# H0BR4.net
KiCad netlist of a schematic drawn in EAGLE
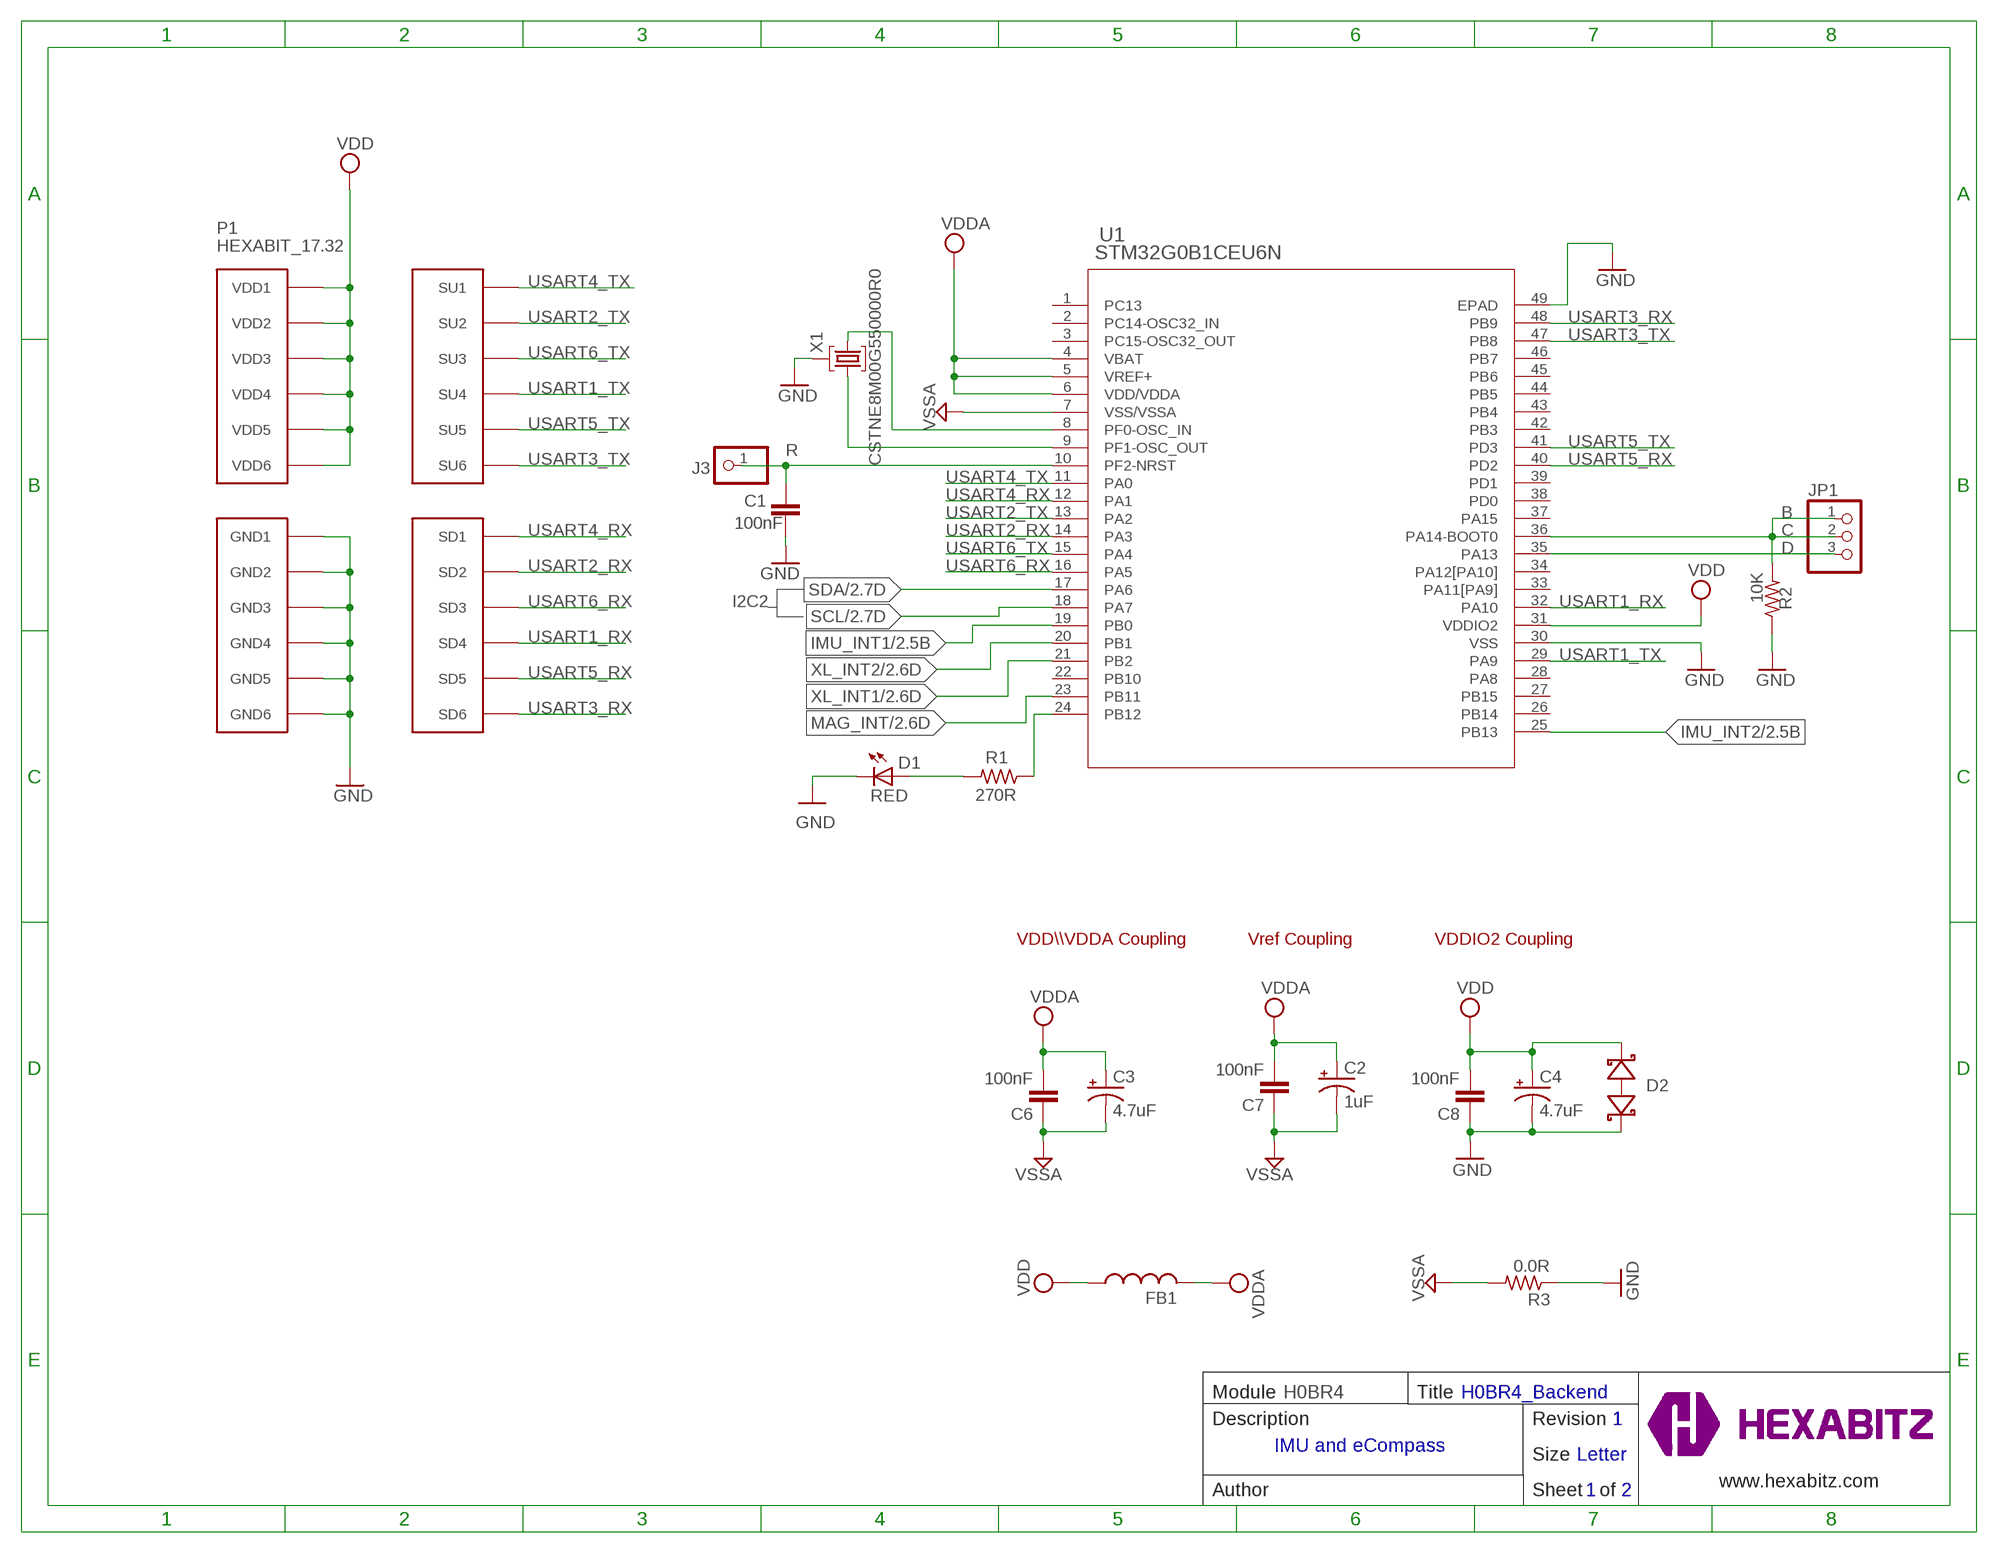
[diagram p0: schematic, sheet 1]
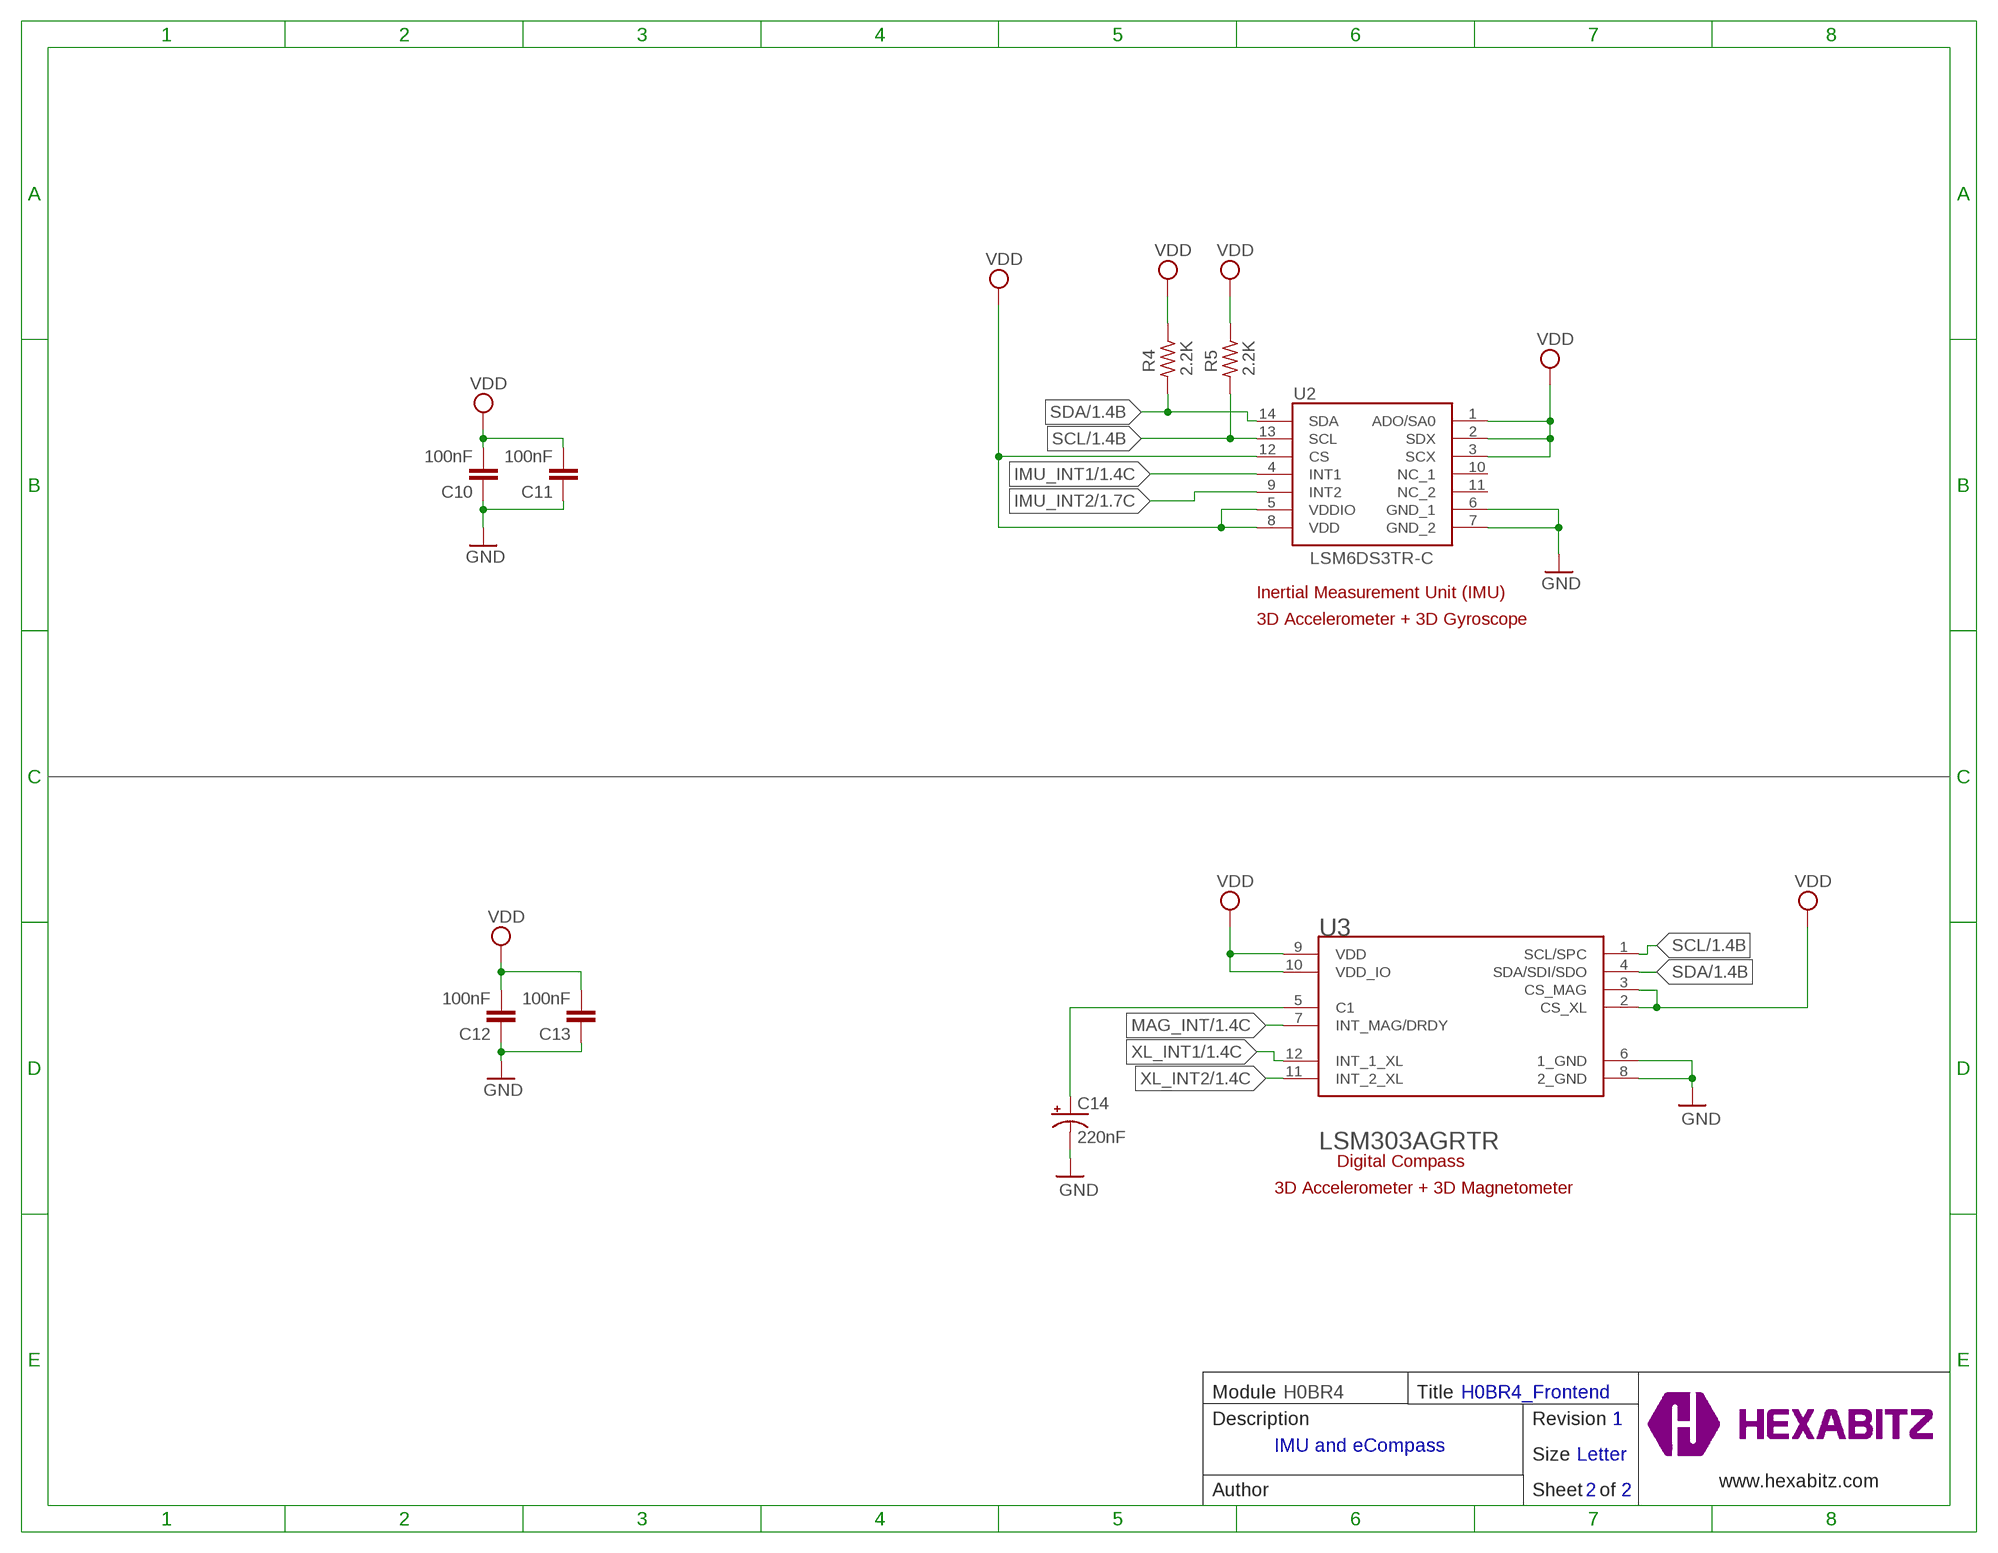
[diagram p1: schematic, sheet 2]

(export (version "E")
  (design (tool "Eeschema 10.0.6"))
  (components
    (comp (ref "C10")
      (value "100nF")
      (footprint "eagle-import:C-0603")
      (fields
        (field (name "CAPACITANCE") "100nF")
        (field (name "MFN") "AVX CORPORATION")
        (field (name "MPN") "'0603YC104K4T2A")
        (field (name "OCTOPART_URL") "'https://octopart.com/0603yc104k4t2a-avx+interconnect+%2F+elco-8120651")
        (field (name "TOLERANCE") "10%")
        (field (name "VOLTAGE_RATING") "16.0 V")
      )
      (libsource (lib "eagle-import") (part "C-0603"))
    )
    (comp (ref "C11")
      (value "100nF")
      (footprint "eagle-import:C-0603")
      (fields
        (field (name "CAPACITANCE") "100nF")
        (field (name "MFN") "AVX CORPORATION")
        (field (name "MPN") "'0603YC104K4T2A")
        (field (name "OCTOPART_URL") "'https://octopart.com/0603yc104k4t2a-avx+interconnect+%2F+elco-8120651")
        (field (name "TOLERANCE") "10%")
        (field (name "VOLTAGE_RATING") "16.0 V")
      )
      (libsource (lib "eagle-import") (part "C-0603"))
    )
    (comp (ref "C12")
      (value "100nF")
      (footprint "eagle-import:C-0603")
      (fields
        (field (name "CAPACITANCE") "100nF")
        (field (name "MFN") "AVX CORPORATION")
        (field (name "MPN") "'0603YC104K4T2A")
        (field (name "OCTOPART_URL") "'https://octopart.com/0603yc104k4t2a-avx+interconnect+%2F+elco-8120651")
        (field (name "TOLERANCE") "10%")
        (field (name "VOLTAGE_RATING") "16.0 V")
      )
      (libsource (lib "eagle-import") (part "C-0603"))
    )
    (comp (ref "C13")
      (value "100nF")
      (footprint "eagle-import:C-0603")
      (fields
        (field (name "CAPACITANCE") "100nF")
        (field (name "MFN") "AVX CORPORATION")
        (field (name "MPN") "'0603YC104K4T2A")
        (field (name "OCTOPART_URL") "'https://octopart.com/0603yc104k4t2a-avx+interconnect+%2F+elco-8120651")
        (field (name "TOLERANCE") "10%")
        (field (name "VOLTAGE_RATING") "16.0 V")
      )
      (libsource (lib "eagle-import") (part "C-0603"))
    )
    (comp (ref "C14")
      (value "220nF")
      (footprint "eagle-import:C-0805-POL")
      (fields
        (field (name "CAPACITANCE") "4.7uF")
        (field (name "MFN") "KEMET ")
        (field (name "MPN") "C0805C224K1RACTU")
        (field (name "OCTOPART_URL") "https://octopart.com/c0805c224k1ractu-kemet-12818106?r=sp")
        (field (name "TOLERANCE") "20%")
        (field (name "VOLTAGE_RATING") "10.0 V")
      )
      (libsource (lib "eagle-import") (part "C-0805-POL"))
    )
    (comp (ref "R4")
      (value "2.2K")
      (footprint "eagle-import:R-0603")
      (fields
        (field (name "MFN") "Yageo")
        (field (name "MPN") "RC0603FR-072K2L")
        (field (name "OCTOPART_URL") "https://octopart.com/rc0603fr-072k2l-yageo-1214512?r=sp")
        (field (name "RESISTANCE") "2.2K Ohm")
        (field (name "TOLERANCE") "5%")
      )
      (libsource (lib "eagle-import") (part "R-0603"))
    )
    (comp (ref "R5")
      (value "2.2K")
      (footprint "eagle-import:R-0603")
      (fields
        (field (name "MFN") "Yageo")
        (field (name "MPN") "RC0603FR-072K2L")
        (field (name "OCTOPART_URL") "https://octopart.com/rc0603fr-072k2l-yageo-1214512?r=sp")
        (field (name "RESISTANCE") "2.2K Ohm")
        (field (name "TOLERANCE") "5%")
      )
      (libsource (lib "eagle-import") (part "R-0603"))
    )
    (comp (ref "U2")
      (value "LSM6DS3TR-C")
      (footprint "eagle-import:LGA-14(2.5X3X0.86)")
      (libsource (lib "eagle-import") (part "LSM6DS3TR-C"))
    )
    (comp (ref "U3")
      (value "STMICROELECTRONICS_LSM303AGRTRSTMICROELECTRONICS_LSM303AGRTR_0_0")
      (footprint "eagle-import:STMICROELECTRONICS_LSM303AGRTR_0")
      (fields
        (field (name "DIGIKEY_PART_NUMBER") "497-16527-1-ND")
        (field (name "MOUSER_PART_NUMBER") "511-LSM303AGRTR")
        (field (name "MPN") "LSM303AGRTR")
      )
      (libsource (lib "eagle-import") (part "STMICROELECTRONICS_LSM303AGRTRSTMICROELECTRONICS_LSM303AGRTR_0_0"))
    )
    (comp (ref "C1")
      (value "100nF")
      (footprint "eagle-import:C-0603")
      (fields
        (field (name "CAPACITANCE") "100nF")
        (field (name "MFN") "AVX CORPORATION")
        (field (name "MPN") "'0603YC104K4T2A")
        (field (name "OCTOPART_URL") "'https://octopart.com/0603yc104k4t2a-avx+interconnect+%2F+elco-8120651")
        (field (name "TOLERANCE") "10%")
        (field (name "VOLTAGE_RATING") "16.0 V")
      )
      (libsource (lib "eagle-import") (part "C-0603"))
    )
    (comp (ref "C2")
      (value "1uF")
      (footprint "eagle-import:C-0805-POL")
      (fields
        (field (name "CAPACITANCE") "1.00uF")
        (field (name "MFN") "'YAGEO [VA]")
        (field (name "MPN") "'CC0805KKX7R7BB105")
        (field (name "OCTOPART_URL") "https://octopart.com/cc0805kkx7r7bb105-yageo-8376555?r=sp")
        (field (name "TOLERANCE") "10%")
        (field (name "VOLTAGE_RATING") "16.0 V")
      )
      (libsource (lib "eagle-import") (part "C-0805-POL"))
    )
    (comp (ref "C3")
      (value "4.7uF")
      (footprint "eagle-import:C-0805-POL")
      (fields
        (field (name "CAPACITANCE") "4.7uF")
        (field (name "MFN") "Panasonic")
        (field (name "MPN") "10TPU4R7MSI")
        (field (name "OCTOPART_URL") "https://octopart.com/10tpu4r7msi-panasonic-29487748")
        (field (name "TOLERANCE") "20%")
        (field (name "VOLTAGE_RATING") "10.0 V")
      )
      (libsource (lib "eagle-import") (part "C-0805-POL"))
    )
    (comp (ref "C4")
      (value "4.7uF")
      (footprint "eagle-import:C-0805-POL")
      (fields
        (field (name "CAPACITANCE") "4.7uF")
        (field (name "MFN") "Panasonic")
        (field (name "MPN") "10TPU4R7MSI")
        (field (name "OCTOPART_URL") "https://octopart.com/10tpu4r7msi-panasonic-29487748")
        (field (name "TOLERANCE") "20%")
        (field (name "VOLTAGE_RATING") "10.0 V")
      )
      (libsource (lib "eagle-import") (part "C-0805-POL"))
    )
    (comp (ref "C6")
      (value "100nF")
      (footprint "eagle-import:C-0603")
      (fields
        (field (name "CAPACITANCE") "100nF")
        (field (name "MFN") "AVX CORPORATION")
        (field (name "MPN") "'0603YC104K4T2A")
        (field (name "OCTOPART_URL") "'https://octopart.com/0603yc104k4t2a-avx+interconnect+%2F+elco-8120651")
        (field (name "TOLERANCE") "10%")
        (field (name "VOLTAGE_RATING") "16.0 V")
      )
      (libsource (lib "eagle-import") (part "C-0603"))
    )
    (comp (ref "C7")
      (value "100nF")
      (footprint "eagle-import:C-0603")
      (fields
        (field (name "CAPACITANCE") "100nF")
        (field (name "MFN") "AVX CORPORATION")
        (field (name "MPN") "'0603YC104K4T2A")
        (field (name "OCTOPART_URL") "'https://octopart.com/0603yc104k4t2a-avx+interconnect+%2F+elco-8120651")
        (field (name "TOLERANCE") "10%")
        (field (name "VOLTAGE_RATING") "16.0 V")
      )
      (libsource (lib "eagle-import") (part "C-0603"))
    )
    (comp (ref "C8")
      (value "100nF")
      (footprint "eagle-import:C-0603")
      (fields
        (field (name "CAPACITANCE") "100nF")
        (field (name "MFN") "AVX CORPORATION")
        (field (name "MPN") "'0603YC104K4T2A")
        (field (name "OCTOPART_URL") "'https://octopart.com/0603yc104k4t2a-avx+interconnect+%2F+elco-8120651")
        (field (name "TOLERANCE") "10%")
        (field (name "VOLTAGE_RATING") "16.0 V")
      )
      (libsource (lib "eagle-import") (part "C-0603"))
    )
    (comp (ref "D1")
      (value "RED")
      (footprint "eagle-import:VLMS1300-GS08")
      (fields (field (name "MPN") "VLMS1300-GS08"))
      (libsource (lib "eagle-import") (part "VLMS1300-GS08"))
    )
    (comp (ref "D2")
      (value "BOURNS_CDSOD323-T03SCBOURNS_CDSOD323-T03SC_0_0")
      (footprint "eagle-import:BOURNS_CDSOD323-T03SC_0")
      (fields (field (name "MPN") "CDSOD323-T03SC"))
      (libsource (lib "eagle-import") (part "BOURNS_CDSOD323-T03SCBOURNS_CDSOD323-T03SC_0_0"))
    )
    (comp (ref "FB1")
      (value "FB-TDK_MMZ1608Y300B")
      (footprint "eagle-import:FB-TDK_MMZ1608Y300B")
      (fields
        (field (name "MFN") "TDK ")
        (field (name "MPN") "MMZ1608Y300BTA00")
        (field (name "OCTOPART_URL") "https://octopart.com/mmz1608y300bta00-tdk-7906990?r=sp")
      )
      (libsource (lib "eagle-import") (part "FB-TDK_MMZ1608Y300B"))
    )
    (comp (ref "J3")
      (value "PINHD-1X1")
      (footprint "eagle-import:1X01")
      (fields (field (name "MPN") "87227-1"))
      (libsource (lib "eagle-import") (part "PINHD-1X1"))
    )
    (comp (ref "JP1")
      (value "PINHD-1X3")
      (footprint "eagle-import:1X03")
      (libsource (lib "eagle-import") (part "PINHD-1X3"))
    )
    (comp (ref "P1")
      (value "HEXABIT_17.32")
      (footprint "eagle-import:HEXABIT_17.32")
      (libsource (lib "eagle-import") (part "HEXABIT_?17.32"))
    )
    (comp (ref "R1")
      (value "270R")
      (footprint "eagle-import:R-0603")
      (fields
        (field (name "MFN") "'Panasonic")
        (field (name "MPN") "'ERJ-3GEYJ271V")
        (field (name "OCTOPART_URL") "https://octopart.com/erj-3geyj271v-panasonic-55560546?r=sp")
        (field (name "RESISTANCE") "270R")
      )
      (libsource (lib "eagle-import") (part "R-0603"))
    )
    (comp (ref "R2")
      (value "10K")
      (footprint "eagle-import:R-0603")
      (fields
        (field (name "MFN") "Vishay")
        (field (name "MPN") "'060300J0103T5E")
        (field (name "OCTOPART_URL") "https://octopart.com/search?q=060300J0103T5E&currency=USD&specs=0")
        (field (name "RESISTANCE") "10K")
      )
      (libsource (lib "eagle-import") (part "R-0603"))
    )
    (comp (ref "R3")
      (value "0.0R")
      (footprint "eagle-import:R-0603")
      (fields
        (field (name "MFN") "YAGEO [VR]")
        (field (name "MPN") "RC0603JR-070RL")
        (field (name "OCTOPART_URL") "https://octopart.com/rc0603jr-070rl-yageo-1241539?r=sp")
        (field (name "RESISTANCE") "0R")
      )
      (libsource (lib "eagle-import") (part "R-0603"))
    )
    (comp (ref "TRIMBLE-LOGO1")
      (value "HEXA-LOGO")
      (footprint "eagle-import:HEXA-LOGO")
      (libsource (lib "eagle-import") (part "HEXA-LOGO"))
    )
    (comp (ref "U1")
      (value "STM32G0B1CEU6N")
      (footprint "eagle-import:HEXABITZ_ICS_QFN_B1CEU6_STM-L")
      (libsource (lib "eagle-import") (part "STM32G0B1CEU6N"))
    )
    (comp (ref "X1")
      (value "CSTNE8M00G550000R0")
      (footprint "eagle-import:XTALL_CSTCE8M00G52")
      (fields
        (field (name "MPN") "CSTCE8M00G52Z-R0")
        (field (name "MPN_1") "CSTNE8M00G550000R0")
        (field (name "OCTOPART_URL") "https://octopart.com/cstne8m00g550000r0-murata-91406934?r=sp")
      )
      (libsource (lib "eagle-import") (part "XTALL_CSTCE8M00G52"))
    )
  )
  (nets
    (net (code "1") (name "C") (class "Default")
      (node (ref "JP1") (pin "1") (pinfunction "1_1") (pintype "passive"))
      (node (ref "JP1") (pin "2") (pinfunction "2_2") (pintype "passive"))
      (node (ref "R2") (pin "2") (pinfunction "2_2") (pintype "passive"))
      (node (ref "U1") (pin "36") (pinfunction "PA14-BOOT0_36") (pintype "bidirectional"))
    )
    (net (code "2") (name "D") (class "Default")
      (node (ref "JP1") (pin "3") (pinfunction "3_3") (pintype "passive"))
      (node (ref "U1") (pin "35") (pinfunction "PA13_35") (pintype "bidirectional"))
    )
    (net (code "3") (name "GND") (class "Default")
      (node (ref "C1") (pin "1") (pinfunction "1_1") (pintype "passive"))
      (node (ref "C10") (pin "1") (pinfunction "1_1") (pintype "passive"))
      (node (ref "C11") (pin "1") (pinfunction "1_1") (pintype "passive"))
      (node (ref "C12") (pin "1") (pinfunction "1_1") (pintype "passive"))
      (node (ref "C13") (pin "1") (pinfunction "1_1") (pintype "passive"))
      (node (ref "C14") (pin "2") (pinfunction "-_2") (pintype "passive"))
      (node (ref "C4") (pin "2") (pinfunction "-_2") (pintype "passive"))
      (node (ref "C8") (pin "1") (pinfunction "1_1") (pintype "passive"))
      (node (ref "D1") (pin "C") (pinfunction "C_C") (pintype "passive"))
      (node (ref "D2") (pin "1") (pinfunction "A_1") (pintype "passive"))
      (node (ref "P1") (pin "PAD_PD10") (pinfunction "GND4_PAD_PD10") (pintype "power_in"))
      (node (ref "P1") (pin "PAD_PD11") (pinfunction "GND5_PAD_PD11") (pintype "power_in"))
      (node (ref "P1") (pin "PAD_PD12") (pinfunction "GND6_PAD_PD12") (pintype "power_in"))
      (node (ref "P1") (pin "PAD_PD7") (pinfunction "GND1_PAD_PD7") (pintype "power_in"))
      (node (ref "P1") (pin "PAD_PD8") (pinfunction "GND2_PAD_PD8") (pintype "power_in"))
      (node (ref "P1") (pin "PAD_PD9") (pinfunction "GND3_PAD_PD9") (pintype "power_in"))
      (node (ref "R2") (pin "1") (pinfunction "1_1") (pintype "passive"))
      (node (ref "R3") (pin "1") (pinfunction "1_1") (pintype "passive"))
      (node (ref "U1") (pin "30") (pinfunction "VSS_30") (pintype "passive"))
      (node (ref "U1") (pin "49") (pinfunction "EPAD_49") (pintype "passive"))
      (node (ref "U2") (pin "6") (pinfunction "GND_1_6") (pintype "bidirectional"))
      (node (ref "U2") (pin "7") (pinfunction "GND_2_7") (pintype "bidirectional"))
      (node (ref "U3") (pin "6") (pinfunction "1_GND_6") (pintype "power_in"))
      (node (ref "U3") (pin "8") (pinfunction "2_GND_8") (pintype "power_in"))
      (node (ref "X1") (pin "P$2") (pinfunction "2_P$2") (pintype "passive"))
    )
    (net (code "4") (name "GND1") (class "Default")
      (node (ref "C2") (pin "2") (pinfunction "-_2") (pintype "passive"))
      (node (ref "C3") (pin "2") (pinfunction "-_2") (pintype "passive"))
      (node (ref "C6") (pin "1") (pinfunction "1_1") (pintype "passive"))
      (node (ref "C7") (pin "1") (pinfunction "1_1") (pintype "passive"))
      (node (ref "R3") (pin "2") (pinfunction "2_2") (pintype "passive"))
      (node (ref "U1") (pin "7") (pinfunction "VSS/VSSA_7") (pintype "passive"))
    )
    (net (code "5") (name "IMU_INT1") (class "Default")
      (node (ref "U1") (pin "19") (pinfunction "PB0_19") (pintype "bidirectional"))
      (node (ref "U2") (pin "4") (pinfunction "INT1_4") (pintype "bidirectional"))
    )
    (net (code "6") (name "IMU_INT2") (class "Default")
      (node (ref "U1") (pin "25") (pinfunction "PB13_25") (pintype "bidirectional"))
      (node (ref "U2") (pin "9") (pinfunction "INT2_9") (pintype "bidirectional"))
    )
    (net (code "7") (name "MAG_INT") (class "Default")
      (node (ref "U1") (pin "23") (pinfunction "PB11_23") (pintype "bidirectional"))
      (node (ref "U3") (pin "7") (pinfunction "INT_MAG/DRDY_7") (pintype "input"))
    )
    (net (code "8") (name "Net-(C14-+)") (class "Default")
      (node (ref "C14") (pin "1") (pinfunction "+_1") (pintype "passive"))
      (node (ref "U3") (pin "5") (pinfunction "C1_5") (pintype "passive"))
    )
    (net (code "9") (name "Net-(D1-PadA)") (class "Default")
      (node (ref "D1") (pin "A") (pinfunction "A_A") (pintype "passive"))
      (node (ref "R1") (pin "2") (pinfunction "2_2") (pintype "passive"))
    )
    (net (code "10") (name "Net-(U1-PB12)") (class "Default")
      (node (ref "R1") (pin "1") (pinfunction "1_1") (pintype "passive"))
      (node (ref "U1") (pin "24") (pinfunction "PB12_24") (pintype "bidirectional"))
    )
    (net (code "11") (name "Net-(U1-PF0-OSC_IN)") (class "Default")
      (node (ref "U1") (pin "8") (pinfunction "PF0-OSC_IN_8") (pintype "bidirectional"))
      (node (ref "X1") (pin "P$1") (pinfunction "1_P$1") (pintype "passive"))
    )
    (net (code "12") (name "Net-(U1-PF1-OSC_OUT)") (class "Default")
      (node (ref "U1") (pin "9") (pinfunction "PF1-OSC_OUT_9") (pintype "bidirectional"))
      (node (ref "X1") (pin "P$3") (pinfunction "3_P$3") (pintype "passive"))
    )
    (net (code "13") (name "R") (class "Default")
      (node (ref "C1") (pin "2") (pinfunction "2_2") (pintype "passive"))
      (node (ref "J3") (pin "1") (pinfunction "1_1") (pintype "passive"))
      (node (ref "U1") (pin "10") (pinfunction "PF2-NRST_10") (pintype "bidirectional"))
    )
    (net (code "14") (name "SCL") (class "Default")
      (node (ref "R5") (pin "2") (pinfunction "2_2") (pintype "passive"))
      (node (ref "U1") (pin "18") (pinfunction "PA7_18") (pintype "bidirectional"))
      (node (ref "U2") (pin "13") (pinfunction "SCL_13") (pintype "bidirectional"))
      (node (ref "U3") (pin "1") (pinfunction "SCL/SPC_1") (pintype "input"))
    )
    (net (code "15") (name "SDA") (class "Default")
      (node (ref "R4") (pin "2") (pinfunction "2_2") (pintype "passive"))
      (node (ref "U1") (pin "17") (pinfunction "PA6_17") (pintype "bidirectional"))
      (node (ref "U2") (pin "14") (pinfunction "SDA_14") (pintype "bidirectional"))
      (node (ref "U3") (pin "4") (pinfunction "SDA/SDI/SDO_4") (pintype "bidirectional"))
    )
    (net (code "16") (name "USART1_RX") (class "Default")
      (node (ref "P1") (pin "PAD_PD4") (pinfunction "SD4_PAD_PD4") (pintype "bidirectional"))
      (node (ref "U1") (pin "32") (pinfunction "PA10_32") (pintype "bidirectional"))
    )
    (net (code "17") (name "USART1_TX") (class "Default")
      (node (ref "P1") (pin "PAD_PU4") (pinfunction "SU4_PAD_PU4") (pintype "bidirectional"))
      (node (ref "U1") (pin "29") (pinfunction "PA9_29") (pintype "bidirectional"))
    )
    (net (code "18") (name "USART2_RX") (class "Default")
      (node (ref "P1") (pin "PAD_PD2") (pinfunction "SD2_PAD_PD2") (pintype "bidirectional"))
      (node (ref "U1") (pin "14") (pinfunction "PA3_14") (pintype "bidirectional"))
    )
    (net (code "19") (name "USART2_TX") (class "Default")
      (node (ref "P1") (pin "PAD_PU2") (pinfunction "SU2_PAD_PU2") (pintype "bidirectional"))
      (node (ref "U1") (pin "13") (pinfunction "PA2_13") (pintype "bidirectional"))
    )
    (net (code "20") (name "USART3_RX") (class "Default")
      (node (ref "P1") (pin "PAD_PD6") (pinfunction "SD6_PAD_PD6") (pintype "bidirectional"))
      (node (ref "U1") (pin "48") (pinfunction "PB9_48") (pintype "bidirectional"))
    )
    (net (code "21") (name "USART3_TX") (class "Default")
      (node (ref "P1") (pin "PAD_PU6") (pinfunction "SU6_PAD_PU6") (pintype "bidirectional"))
      (node (ref "U1") (pin "47") (pinfunction "PB8_47") (pintype "bidirectional"))
    )
    (net (code "22") (name "USART4_RX") (class "Default")
      (node (ref "P1") (pin "PAD_PD1") (pinfunction "SD1_PAD_PD1") (pintype "bidirectional"))
      (node (ref "U1") (pin "12") (pinfunction "PA1_12") (pintype "bidirectional"))
    )
    (net (code "23") (name "USART4_TX") (class "Default")
      (node (ref "P1") (pin "PAD_PU1") (pinfunction "SU1_PAD_PU1") (pintype "bidirectional"))
      (node (ref "U1") (pin "11") (pinfunction "PA0_11") (pintype "bidirectional"))
    )
    (net (code "24") (name "USART5_RX") (class "Default")
      (node (ref "P1") (pin "PAD_PD5") (pinfunction "SD5_PAD_PD5") (pintype "bidirectional"))
      (node (ref "U1") (pin "40") (pinfunction "PD2_40") (pintype "bidirectional"))
    )
    (net (code "25") (name "USART5_TX") (class "Default")
      (node (ref "P1") (pin "PAD_PU5") (pinfunction "SU5_PAD_PU5") (pintype "bidirectional"))
      (node (ref "U1") (pin "41") (pinfunction "PD3_41") (pintype "bidirectional"))
    )
    (net (code "26") (name "USART6_RX") (class "Default")
      (node (ref "P1") (pin "PAD_PD3") (pinfunction "SD3_PAD_PD3") (pintype "bidirectional"))
      (node (ref "U1") (pin "16") (pinfunction "PA5_16") (pintype "bidirectional"))
    )
    (net (code "27") (name "USART6_TX") (class "Default")
      (node (ref "P1") (pin "PAD_PU3") (pinfunction "SU3_PAD_PU3") (pintype "bidirectional"))
      (node (ref "U1") (pin "15") (pinfunction "PA4_15") (pintype "bidirectional"))
    )
    (net (code "28") (name "VCC") (class "Default")
      (node (ref "C2") (pin "1") (pinfunction "+_1") (pintype "passive"))
      (node (ref "C3") (pin "1") (pinfunction "+_1") (pintype "passive"))
      (node (ref "C6") (pin "2") (pinfunction "2_2") (pintype "passive"))
      (node (ref "C7") (pin "2") (pinfunction "2_2") (pintype "passive"))
      (node (ref "FB1") (pin "2") (pinfunction "2_2") (pintype "passive"))
      (node (ref "U1") (pin "4") (pinfunction "VBAT_4") (pintype "power_in"))
      (node (ref "U1") (pin "5") (pinfunction "VREF+_5") (pintype "power_in"))
      (node (ref "U1") (pin "6") (pinfunction "VDD/VDDA_6") (pintype "power_in"))
    )
    (net (code "29") (name "VDD") (class "Default")
      (node (ref "C10") (pin "2") (pinfunction "2_2") (pintype "passive"))
      (node (ref "C11") (pin "2") (pinfunction "2_2") (pintype "passive"))
      (node (ref "C12") (pin "2") (pinfunction "2_2") (pintype "passive"))
      (node (ref "C13") (pin "2") (pinfunction "2_2") (pintype "passive"))
      (node (ref "C4") (pin "1") (pinfunction "+_1") (pintype "passive"))
      (node (ref "C8") (pin "2") (pinfunction "2_2") (pintype "passive"))
      (node (ref "D2") (pin "2") (pinfunction "C_2") (pintype "passive"))
      (node (ref "FB1") (pin "1") (pinfunction "1_1") (pintype "passive"))
      (node (ref "P1") (pin "PAD_PU10") (pinfunction "VDD4_PAD_PU10") (pintype "power_in"))
      (node (ref "P1") (pin "PAD_PU11") (pinfunction "VDD5_PAD_PU11") (pintype "power_in"))
      (node (ref "P1") (pin "PAD_PU12") (pinfunction "VDD6_PAD_PU12") (pintype "power_in"))
      (node (ref "P1") (pin "PAD_PU7") (pinfunction "VDD1_PAD_PU7") (pintype "power_in"))
      (node (ref "P1") (pin "PAD_PU8") (pinfunction "VDD2_PAD_PU8") (pintype "power_in"))
      (node (ref "P1") (pin "PAD_PU9") (pinfunction "VDD3_PAD_PU9") (pintype "power_in"))
      (node (ref "R4") (pin "1") (pinfunction "1_1") (pintype "passive"))
      (node (ref "R5") (pin "1") (pinfunction "1_1") (pintype "passive"))
      (node (ref "U1") (pin "31") (pinfunction "VDDIO2_31") (pintype "power_in"))
      (node (ref "U2") (pin "1") (pinfunction "ADO/SA0_1") (pintype "bidirectional"))
      (node (ref "U2") (pin "12") (pinfunction "CS_12") (pintype "bidirectional"))
      (node (ref "U2") (pin "2") (pinfunction "SDX_2") (pintype "bidirectional"))
      (node (ref "U2") (pin "3") (pinfunction "SCX_3") (pintype "bidirectional"))
      (node (ref "U2") (pin "5") (pinfunction "VDDIO_5") (pintype "bidirectional"))
      (node (ref "U2") (pin "8") (pinfunction "VDD_8") (pintype "bidirectional"))
      (node (ref "U3") (pin "10") (pinfunction "VDD_IO_10") (pintype "power_in"))
      (node (ref "U3") (pin "2") (pinfunction "CS_XL_2") (pintype "input"))
      (node (ref "U3") (pin "3") (pinfunction "CS_MAG_3") (pintype "input"))
      (node (ref "U3") (pin "9") (pinfunction "VDD_9") (pintype "power_in"))
    )
    (net (code "30") (name "XL_INT1") (class "Default")
      (node (ref "U1") (pin "21") (pinfunction "PB2_21") (pintype "bidirectional"))
      (node (ref "U3") (pin "12") (pinfunction "INT_1_XL_12") (pintype "input"))
    )
    (net (code "31") (name "XL_INT2") (class "Default")
      (node (ref "U1") (pin "20") (pinfunction "PB1_20") (pintype "bidirectional"))
      (node (ref "U3") (pin "11") (pinfunction "INT_2_XL_11") (pintype "input"))
    )
    (net (code "32") (name "unconnected-(U1-PA8-Pad28)") (class "Default")
      (node (ref "U1") (pin "28") (pinfunction "PA8_28") (pintype "bidirectional"))
    )
    (net (code "33") (name "unconnected-(U1-PA11[PA9]-Pad33)") (class "Default")
      (node (ref "U1") (pin "33") (pinfunction "PA11[PA9]_33") (pintype "bidirectional"))
    )
    (net (code "34") (name "unconnected-(U1-PA12[PA10]-Pad34)") (class "Default")
      (node (ref "U1") (pin "34") (pinfunction "PA12[PA10]_34") (pintype "bidirectional"))
    )
    (net (code "35") (name "unconnected-(U1-PA15-Pad37)") (class "Default")
      (node (ref "U1") (pin "37") (pinfunction "PA15_37") (pintype "bidirectional"))
    )
    (net (code "36") (name "unconnected-(U1-PB3-Pad42)") (class "Default")
      (node (ref "U1") (pin "42") (pinfunction "PB3_42") (pintype "bidirectional"))
    )
    (net (code "37") (name "unconnected-(U1-PB4-Pad43)") (class "Default")
      (node (ref "U1") (pin "43") (pinfunction "PB4_43") (pintype "bidirectional"))
    )
    (net (code "38") (name "unconnected-(U1-PB5-Pad44)") (class "Default")
      (node (ref "U1") (pin "44") (pinfunction "PB5_44") (pintype "bidirectional"))
    )
    (net (code "39") (name "unconnected-(U1-PB6-Pad45)") (class "Default")
      (node (ref "U1") (pin "45") (pinfunction "PB6_45") (pintype "bidirectional"))
    )
    (net (code "40") (name "unconnected-(U1-PB7-Pad46)") (class "Default")
      (node (ref "U1") (pin "46") (pinfunction "PB7_46") (pintype "bidirectional"))
    )
    (net (code "41") (name "unconnected-(U1-PB10-Pad22)") (class "Default")
      (node (ref "U1") (pin "22") (pinfunction "PB10_22") (pintype "bidirectional"))
    )
    (net (code "42") (name "unconnected-(U1-PB14-Pad26)") (class "Default")
      (node (ref "U1") (pin "26") (pinfunction "PB14_26") (pintype "bidirectional"))
    )
    (net (code "43") (name "unconnected-(U1-PB15-Pad27)") (class "Default")
      (node (ref "U1") (pin "27") (pinfunction "PB15_27") (pintype "bidirectional"))
    )
    (net (code "44") (name "unconnected-(U1-PC13-Pad1)") (class "Default")
      (node (ref "U1") (pin "1") (pinfunction "PC13_1") (pintype "bidirectional"))
    )
    (net (code "45") (name "unconnected-(U1-PC14-OSC32_IN-Pad2)") (class "Default")
      (node (ref "U1") (pin "2") (pinfunction "PC14-OSC32_IN_2") (pintype "bidirectional"))
    )
    (net (code "46") (name "unconnected-(U1-PC15-OSC32_OUT-Pad3)") (class "Default")
      (node (ref "U1") (pin "3") (pinfunction "PC15-OSC32_OUT_3") (pintype "bidirectional"))
    )
    (net (code "47") (name "unconnected-(U1-PD0-Pad38)") (class "Default")
      (node (ref "U1") (pin "38") (pinfunction "PD0_38") (pintype "bidirectional"))
    )
    (net (code "48") (name "unconnected-(U1-PD1-Pad39)") (class "Default")
      (node (ref "U1") (pin "39") (pinfunction "PD1_39") (pintype "bidirectional"))
    )
    (net (code "49") (name "unconnected-(U2-NC_1-Pad10)") (class "Default")
      (node (ref "U2") (pin "10") (pinfunction "NC_1_10") (pintype "bidirectional"))
    )
    (net (code "50") (name "unconnected-(U2-NC_2-Pad11)") (class "Default")
      (node (ref "U2") (pin "11") (pinfunction "NC_2_11") (pintype "bidirectional"))
    )
  )
)
